# gear_indicator_v1_0.net
KiCad netlist of a schematic drawn in EAGLE
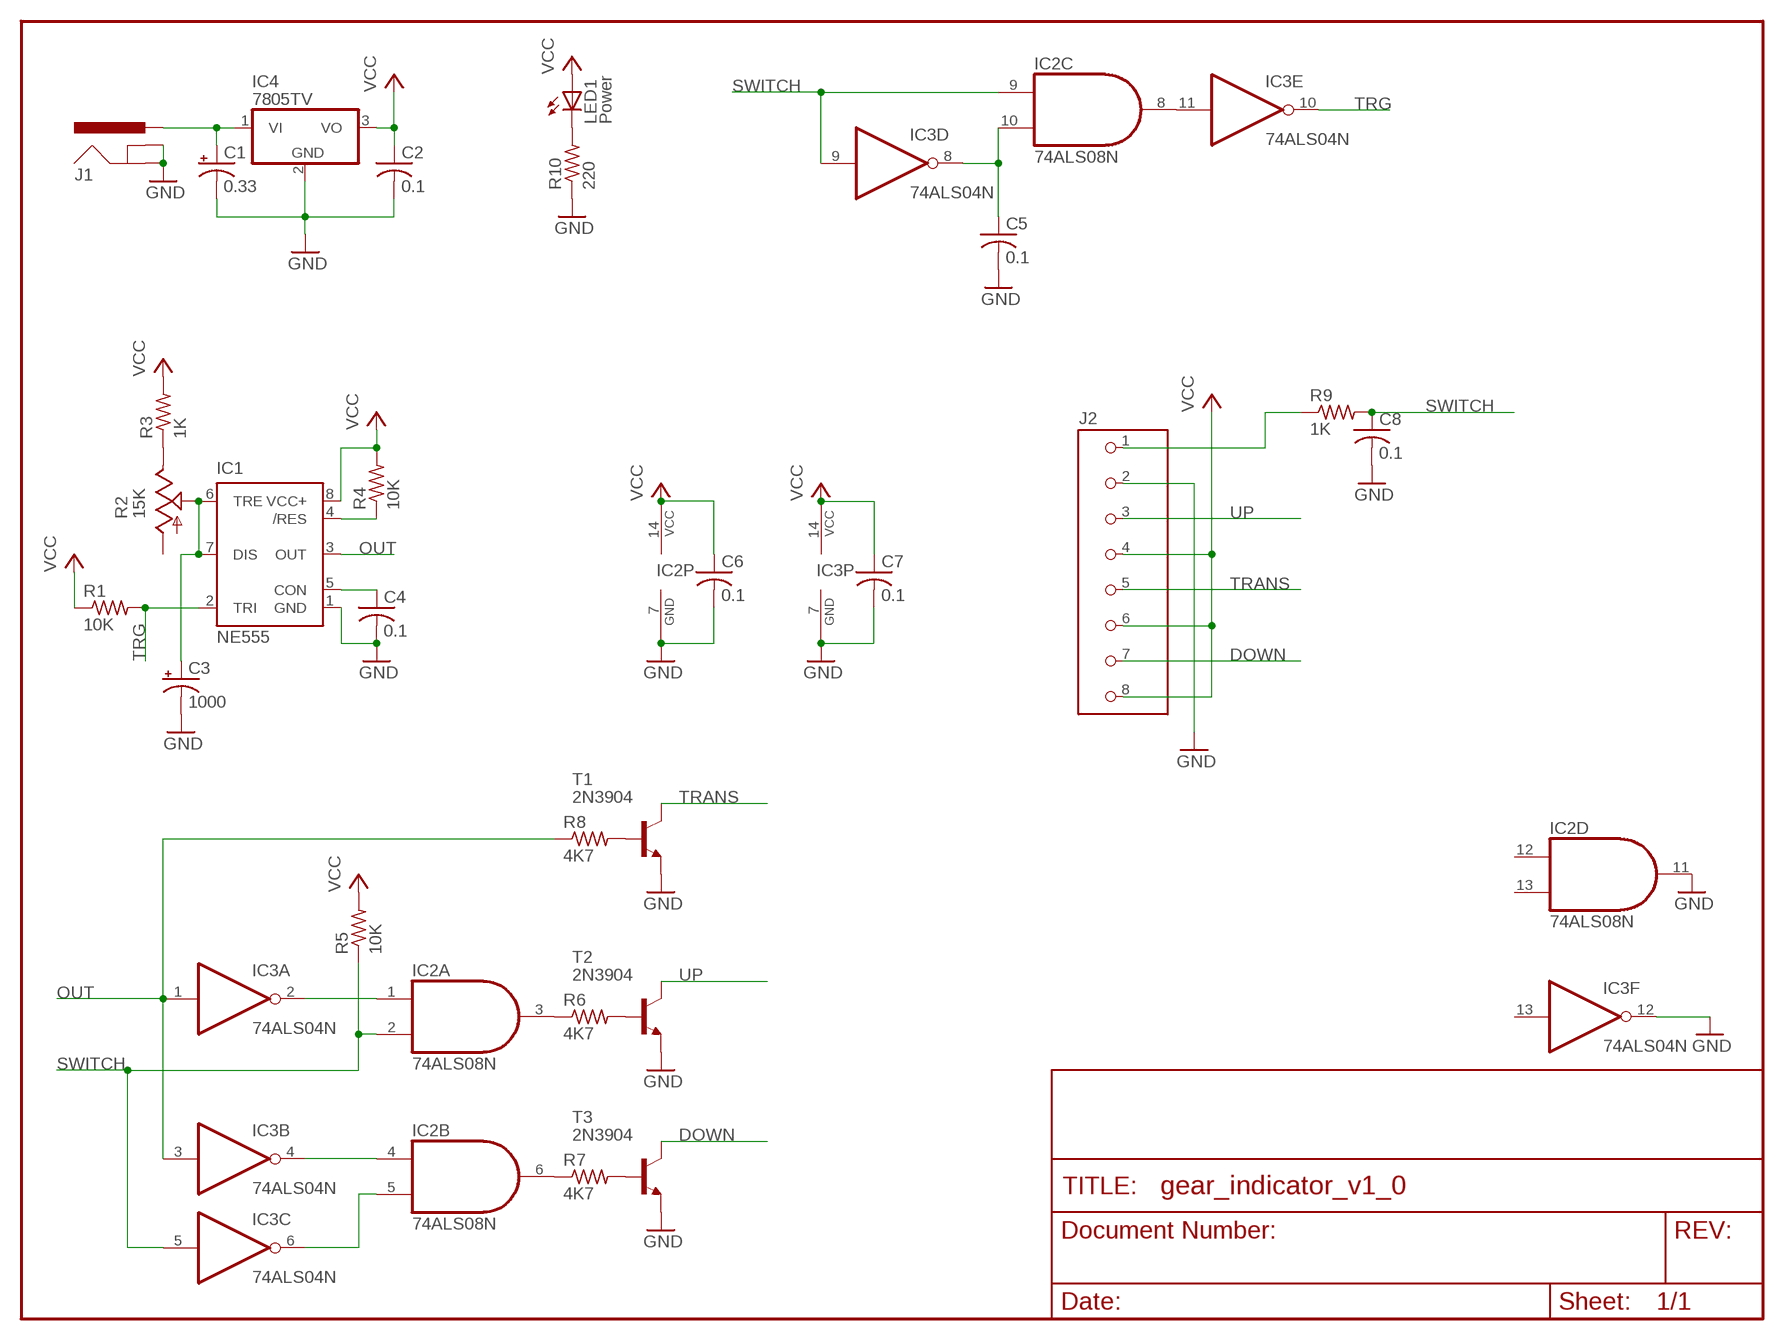
[diagram p0: schematic, sheet 1]

(export (version "E")
  (design (tool "Eeschema 10.0.6"))
  (components
    (comp (ref "C1")
      (value "0.33")
      (footprint "eagle-import:E2,5-6")
      (libsource (lib "eagle-import") (part "CPOL-USE2.5-6"))
    )
    (comp (ref "C2")
      (value "0.1")
      (footprint "eagle-import:C025-025X050")
      (libsource (lib "eagle-import") (part "C-US025-025X050"))
    )
    (comp (ref "C3")
      (value "1000")
      (footprint "eagle-import:E3,5-10")
      (libsource (lib "eagle-import") (part "CPOL-USE3.5-10"))
    )
    (comp (ref "C4")
      (value "0.1")
      (footprint "eagle-import:C025-025X050")
      (libsource (lib "eagle-import") (part "C-US025-025X050"))
    )
    (comp (ref "C5")
      (value "0.1")
      (footprint "eagle-import:C025-025X050")
      (libsource (lib "eagle-import") (part "C-US025-025X050"))
    )
    (comp (ref "C6")
      (value "0.1")
      (footprint "eagle-import:C025-025X050")
      (libsource (lib "eagle-import") (part "C-US025-025X050"))
    )
    (comp (ref "C7")
      (value "0.1")
      (footprint "eagle-import:C025-025X050")
      (libsource (lib "eagle-import") (part "C-US025-025X050"))
    )
    (comp (ref "C8")
      (value "0.1")
      (footprint "eagle-import:C025-025X050")
      (libsource (lib "eagle-import") (part "C-US025-025X050"))
    )
    (comp (ref "IC1")
      (value "NE555")
      (footprint "eagle-import:DIL-08")
      (libsource (lib "eagle-import") (part "NE555"))
    )
    (comp (ref "IC2")
      (value "74ALS08N")
      (footprint "eagle-import:DIL14")
      (libsource (lib "eagle-import") (part "7408NALS"))
    )
    (comp (ref "IC3")
      (value "74ALS04N")
      (footprint "eagle-import:DIL14")
      (libsource (lib "eagle-import") (part "7404NALS"))
    )
    (comp (ref "IC4")
      (value "7805TV")
      (footprint "eagle-import:TO220V")
      (libsource (lib "eagle-import") (part "78TV05"))
    )
    (comp (ref "J1")
      (value "POWER_JACKPTH")
      (footprint "eagle-import:POWER_JACK_PTH")
      (libsource (lib "eagle-import") (part "POWER_JACKPTH"))
    )
    (comp (ref "J2")
      (value "TERMBLOCKX8")
      (footprint "eagle-import:TERMBLOCKX8")
      (libsource (lib "eagle-import") (part "TERMBLOCKX8"))
    )
    (comp (ref "LED1")
      (value "Power")
      (footprint "eagle-import:LED-3MM")
      (libsource (lib "eagle-import") (part "LED3MM"))
    )
    (comp (ref "R1")
      (value "10K")
      (footprint "eagle-import:0207_7")
      (libsource (lib "eagle-import") (part "R-US_0207/7"))
    )
    (comp (ref "R2")
      (value "15K")
      (footprint "eagle-import:B25P")
      (libsource (lib "eagle-import") (part "TRIM_US-B25P"))
    )
    (comp (ref "R3")
      (value "1K")
      (footprint "eagle-import:0207_7")
      (libsource (lib "eagle-import") (part "R-US_0207/7"))
    )
    (comp (ref "R4")
      (value "10K")
      (footprint "eagle-import:0207_7")
      (libsource (lib "eagle-import") (part "R-US_0207/7"))
    )
    (comp (ref "R5")
      (value "10K")
      (footprint "eagle-import:0207_7")
      (libsource (lib "eagle-import") (part "R-US_0207/7"))
    )
    (comp (ref "R6")
      (value "4K7")
      (footprint "eagle-import:0207_7")
      (libsource (lib "eagle-import") (part "R-US_0207/7"))
    )
    (comp (ref "R7")
      (value "4K7")
      (footprint "eagle-import:0207_7")
      (libsource (lib "eagle-import") (part "R-US_0207/7"))
    )
    (comp (ref "R8")
      (value "4K7")
      (footprint "eagle-import:0207_7")
      (libsource (lib "eagle-import") (part "R-US_0207/7"))
    )
    (comp (ref "R9")
      (value "1K")
      (footprint "eagle-import:0207_7")
      (libsource (lib "eagle-import") (part "R-US_0207/7"))
    )
    (comp (ref "R10")
      (value "220")
      (footprint "eagle-import:0207_7")
      (libsource (lib "eagle-import") (part "R-US_0207/7"))
    )
    (comp (ref "T1")
      (value "2N3904")
      (footprint "eagle-import:TO92")
      (libsource (lib "eagle-import") (part "2N3904"))
    )
    (comp (ref "T2")
      (value "2N3904")
      (footprint "eagle-import:TO92")
      (libsource (lib "eagle-import") (part "2N3904"))
    )
    (comp (ref "T3")
      (value "2N3904")
      (footprint "eagle-import:TO92")
      (libsource (lib "eagle-import") (part "2N3904"))
    )
  )
  (nets
    (net (code "1") (name "/DOWN") (class "Default")
      (node (ref "J2") (pin "7") (pinfunction "7_7") (pintype "passive"))
      (node (ref "T3") (pin "1") (pinfunction "C_1") (pintype "passive"))
    )
    (net (code "2") (name "/OUT") (class "Default")
      (node (ref "IC1") (pin "3") (pinfunction "OUT_3") (pintype "output"))
      (node (ref "IC3") (pin "1") (pinfunction "I_1") (pintype "input"))
      (node (ref "IC3") (pin "3") (pinfunction "I_3") (pintype "input"))
      (node (ref "R8") (pin "1") (pinfunction "1_1") (pintype "passive"))
    )
    (net (code "3") (name "/SWITCH") (class "Default")
      (node (ref "C8") (pin "1") (pinfunction "1_1") (pintype "passive"))
      (node (ref "IC2") (pin "2") (pinfunction "I1_2") (pintype "input"))
      (node (ref "IC2") (pin "9") (pinfunction "I0_9") (pintype "input"))
      (node (ref "IC3") (pin "5") (pinfunction "I_5") (pintype "input"))
      (node (ref "IC3") (pin "9") (pinfunction "I_9") (pintype "input"))
      (node (ref "R5") (pin "1") (pinfunction "1_1") (pintype "passive"))
      (node (ref "R9") (pin "2") (pinfunction "2_2") (pintype "passive"))
    )
    (net (code "4") (name "/TRANS") (class "Default")
      (node (ref "J2") (pin "5") (pinfunction "5_5") (pintype "passive"))
      (node (ref "T1") (pin "1") (pinfunction "C_1") (pintype "passive"))
    )
    (net (code "5") (name "/TRG") (class "Default")
      (node (ref "IC1") (pin "2") (pinfunction "TRI_2") (pintype "input"))
      (node (ref "IC3") (pin "10") (pinfunction "O_10") (pintype "output"))
      (node (ref "R1") (pin "2") (pinfunction "2_2") (pintype "passive"))
    )
    (net (code "6") (name "/UP") (class "Default")
      (node (ref "J2") (pin "3") (pinfunction "3_3") (pintype "passive"))
      (node (ref "T2") (pin "1") (pinfunction "C_1") (pintype "passive"))
    )
    (net (code "7") (name "GND") (class "Default")
      (node (ref "C1") (pin "-") (pinfunction "-_-") (pintype "passive"))
      (node (ref "C2") (pin "2") (pinfunction "2_2") (pintype "passive"))
      (node (ref "C3") (pin "-") (pinfunction "-_-") (pintype "passive"))
      (node (ref "C4") (pin "2") (pinfunction "2_2") (pintype "passive"))
      (node (ref "C5") (pin "2") (pinfunction "2_2") (pintype "passive"))
      (node (ref "C6") (pin "2") (pinfunction "2_2") (pintype "passive"))
      (node (ref "C7") (pin "2") (pinfunction "2_2") (pintype "passive"))
      (node (ref "C8") (pin "2") (pinfunction "2_2") (pintype "passive"))
      (node (ref "IC1") (pin "1") (pinfunction "GND_1") (pintype "power_in"))
      (node (ref "IC2") (pin "11") (pinfunction "O_11") (pintype "output"))
      (node (ref "IC2") (pin "7") (pinfunction "GND_7") (pintype "power_in"))
      (node (ref "IC3") (pin "12") (pinfunction "O_12") (pintype "output"))
      (node (ref "IC3") (pin "7") (pinfunction "GND_7") (pintype "power_in"))
      (node (ref "IC4") (pin "2") (pinfunction "GND_2") (pintype "passive"))
      (node (ref "J1") (pin "GND") (pinfunction "GND_GND") (pintype "bidirectional"))
      (node (ref "J1") (pin "GNDBREAK") (pinfunction "GNDBREAK_GNDBREAK") (pintype "bidirectional"))
      (node (ref "J2") (pin "2") (pinfunction "2_2") (pintype "passive"))
      (node (ref "R10") (pin "1") (pinfunction "1_1") (pintype "passive"))
      (node (ref "T1") (pin "3") (pinfunction "E_3") (pintype "passive"))
      (node (ref "T2") (pin "3") (pinfunction "E_3") (pintype "passive"))
      (node (ref "T3") (pin "3") (pinfunction "E_3") (pintype "passive"))
    )
    (net (code "8") (name "Net-(IC1-CON)") (class "Default")
      (node (ref "C4") (pin "1") (pinfunction "1_1") (pintype "passive"))
      (node (ref "IC1") (pin "5") (pinfunction "CON_5") (pintype "input"))
    )
    (net (code "9") (name "Net-(IC1-DIS)") (class "Default")
      (node (ref "C3") (pin "+") (pinfunction "+_+") (pintype "passive"))
      (node (ref "IC1") (pin "6") (pinfunction "TRE_6") (pintype "input"))
      (node (ref "IC1") (pin "7") (pinfunction "DIS_7") (pintype "input"))
      (node (ref "R2") (pin "S") (pinfunction "S_S") (pintype "passive"))
    )
    (net (code "10") (name "Net-(IC1-{slash}RES)") (class "Default")
      (node (ref "IC1") (pin "4") (pinfunction "/RES_4") (pintype "input"))
      (node (ref "R4") (pin "1") (pinfunction "1_1") (pintype "passive"))
    )
    (net (code "11") (name "Net-(IC2A-I0)") (class "Default")
      (node (ref "IC2") (pin "1") (pinfunction "I0_1") (pintype "input"))
      (node (ref "IC3") (pin "2") (pinfunction "O_2") (pintype "output"))
    )
    (net (code "12") (name "Net-(IC2A-O)") (class "Default")
      (node (ref "IC2") (pin "3") (pinfunction "O_3") (pintype "output"))
      (node (ref "R6") (pin "1") (pinfunction "1_1") (pintype "passive"))
    )
    (net (code "13") (name "Net-(IC2B-I0)") (class "Default")
      (node (ref "IC2") (pin "4") (pinfunction "I0_4") (pintype "input"))
      (node (ref "IC3") (pin "4") (pinfunction "O_4") (pintype "output"))
    )
    (net (code "14") (name "Net-(IC2B-I1)") (class "Default")
      (node (ref "IC2") (pin "5") (pinfunction "I1_5") (pintype "input"))
      (node (ref "IC3") (pin "6") (pinfunction "O_6") (pintype "output"))
    )
    (net (code "15") (name "Net-(IC2B-O)") (class "Default")
      (node (ref "IC2") (pin "6") (pinfunction "O_6") (pintype "output"))
      (node (ref "R7") (pin "1") (pinfunction "1_1") (pintype "passive"))
    )
    (net (code "16") (name "Net-(IC2C-I1)") (class "Default")
      (node (ref "C5") (pin "1") (pinfunction "1_1") (pintype "passive"))
      (node (ref "IC2") (pin "10") (pinfunction "I1_10") (pintype "input"))
      (node (ref "IC3") (pin "8") (pinfunction "O_8") (pintype "output"))
    )
    (net (code "17") (name "Net-(IC2C-O)") (class "Default")
      (node (ref "IC2") (pin "8") (pinfunction "O_8") (pintype "output"))
      (node (ref "IC3") (pin "11") (pinfunction "I_11") (pintype "input"))
    )
    (net (code "18") (name "Net-(IC4-VI)") (class "Default")
      (node (ref "C1") (pin "+") (pinfunction "+_+") (pintype "passive"))
      (node (ref "IC4") (pin "1") (pinfunction "VI_1") (pintype "input"))
      (node (ref "J1") (pin "PWR") (pinfunction "PWR_PWR") (pintype "bidirectional"))
    )
    (net (code "19") (name "Net-(J2-Pad1)") (class "Default")
      (node (ref "J2") (pin "1") (pinfunction "1_1") (pintype "passive"))
      (node (ref "R9") (pin "1") (pinfunction "1_1") (pintype "passive"))
    )
    (net (code "20") (name "Net-(LED1-C)") (class "Default")
      (node (ref "LED1") (pin "K") (pinfunction "C_K") (pintype "passive"))
      (node (ref "R10") (pin "2") (pinfunction "2_2") (pintype "passive"))
    )
    (net (code "21") (name "Net-(R2-PadE)") (class "Default")
      (node (ref "R2") (pin "E") (pinfunction "E_E") (pintype "passive"))
      (node (ref "R3") (pin "1") (pinfunction "1_1") (pintype "passive"))
    )
    (net (code "22") (name "Net-(T1-B)") (class "Default")
      (node (ref "R8") (pin "2") (pinfunction "2_2") (pintype "passive"))
      (node (ref "T1") (pin "2") (pinfunction "B_2") (pintype "passive"))
    )
    (net (code "23") (name "Net-(T2-B)") (class "Default")
      (node (ref "R6") (pin "2") (pinfunction "2_2") (pintype "passive"))
      (node (ref "T2") (pin "2") (pinfunction "B_2") (pintype "passive"))
    )
    (net (code "24") (name "Net-(T3-B)") (class "Default")
      (node (ref "R7") (pin "2") (pinfunction "2_2") (pintype "passive"))
      (node (ref "T3") (pin "2") (pinfunction "B_2") (pintype "passive"))
    )
    (net (code "25") (name "VCC") (class "Default")
      (node (ref "C2") (pin "1") (pinfunction "1_1") (pintype "passive"))
      (node (ref "C6") (pin "1") (pinfunction "1_1") (pintype "passive"))
      (node (ref "C7") (pin "1") (pinfunction "1_1") (pintype "passive"))
      (node (ref "IC1") (pin "8") (pinfunction "VCC+_8") (pintype "power_in"))
      (node (ref "IC2") (pin "14") (pinfunction "VCC_14") (pintype "power_in"))
      (node (ref "IC3") (pin "14") (pinfunction "VCC_14") (pintype "power_in"))
      (node (ref "IC4") (pin "3") (pinfunction "VO_3") (pintype "passive"))
      (node (ref "J2") (pin "4") (pinfunction "4_4") (pintype "passive"))
      (node (ref "J2") (pin "6") (pinfunction "6_6") (pintype "passive"))
      (node (ref "J2") (pin "8") (pinfunction "8_8") (pintype "passive"))
      (node (ref "LED1") (pin "A") (pinfunction "A_A") (pintype "passive"))
      (node (ref "R1") (pin "1") (pinfunction "1_1") (pintype "passive"))
      (node (ref "R3") (pin "2") (pinfunction "2_2") (pintype "passive"))
      (node (ref "R4") (pin "2") (pinfunction "2_2") (pintype "passive"))
      (node (ref "R5") (pin "2") (pinfunction "2_2") (pintype "passive"))
    )
    (net (code "26") (name "unconnected-(IC2D-I0-Pad12)") (class "Default")
      (node (ref "IC2") (pin "12") (pinfunction "I0_12") (pintype "input"))
    )
    (net (code "27") (name "unconnected-(IC2D-I1-Pad13)") (class "Default")
      (node (ref "IC2") (pin "13") (pinfunction "I1_13") (pintype "input"))
    )
    (net (code "28") (name "unconnected-(IC3F-I-Pad13)") (class "Default")
      (node (ref "IC3") (pin "13") (pinfunction "I_13") (pintype "input"))
    )
    (net (code "29") (name "unconnected-(R2-PadA)") (class "Default")
      (node (ref "R2") (pin "A") (pinfunction "A_A") (pintype "passive"))
    )
  )
)
